# projet_pcb_nucleo_g431.net
KiCad netlist of a schematic drawn in Altium Designer
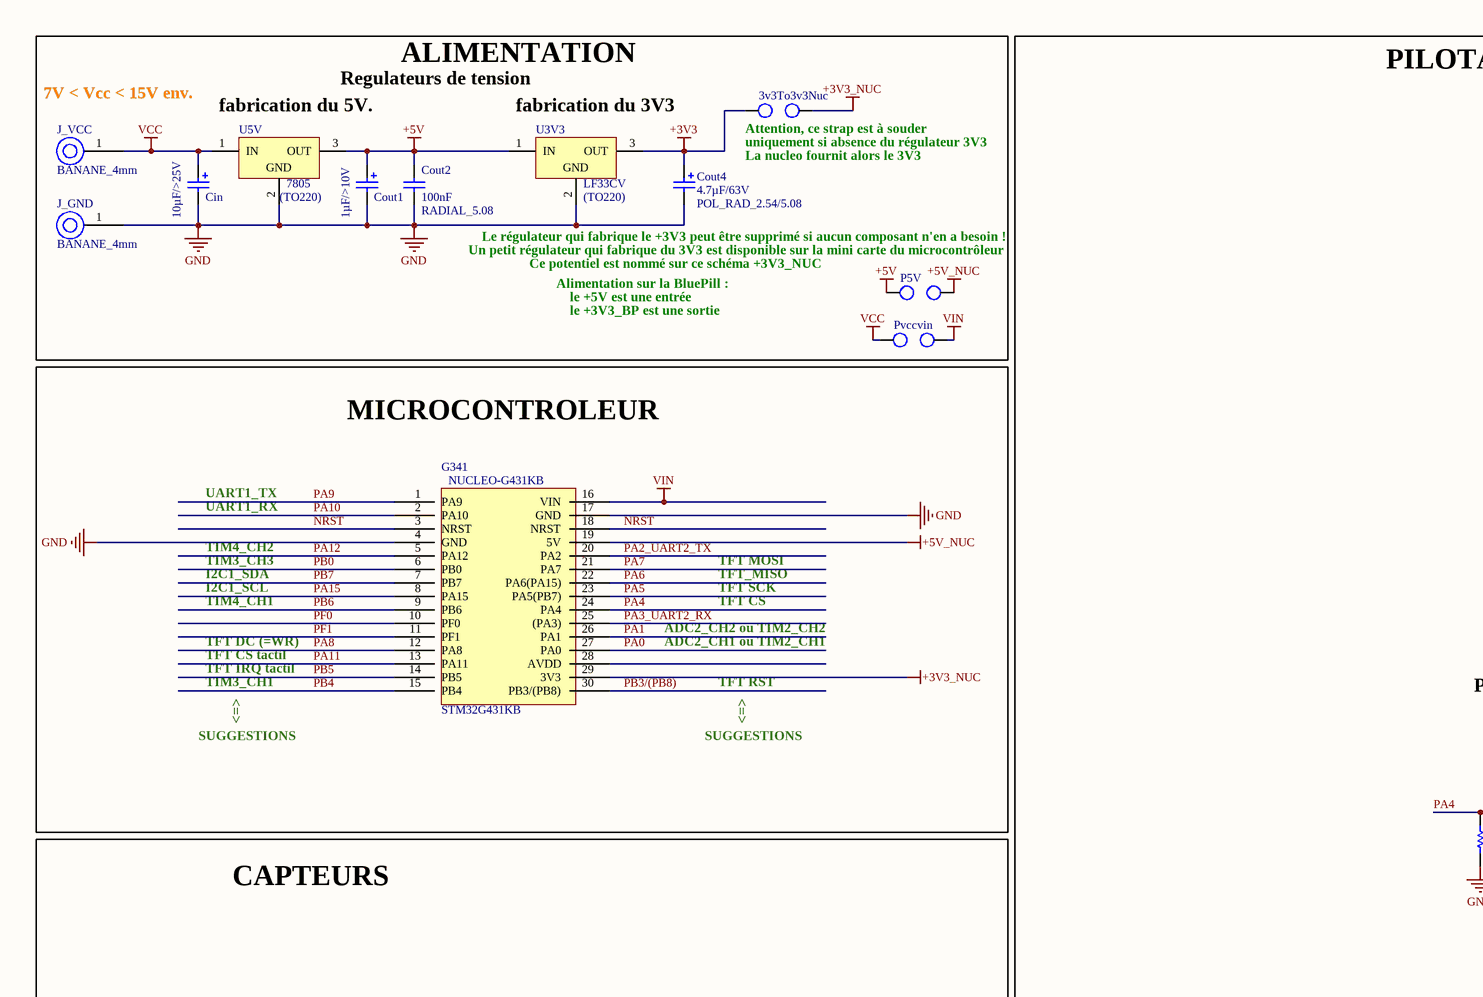
[diagram p0: projet_pcb_nucleo_g431.SchDoc, left]
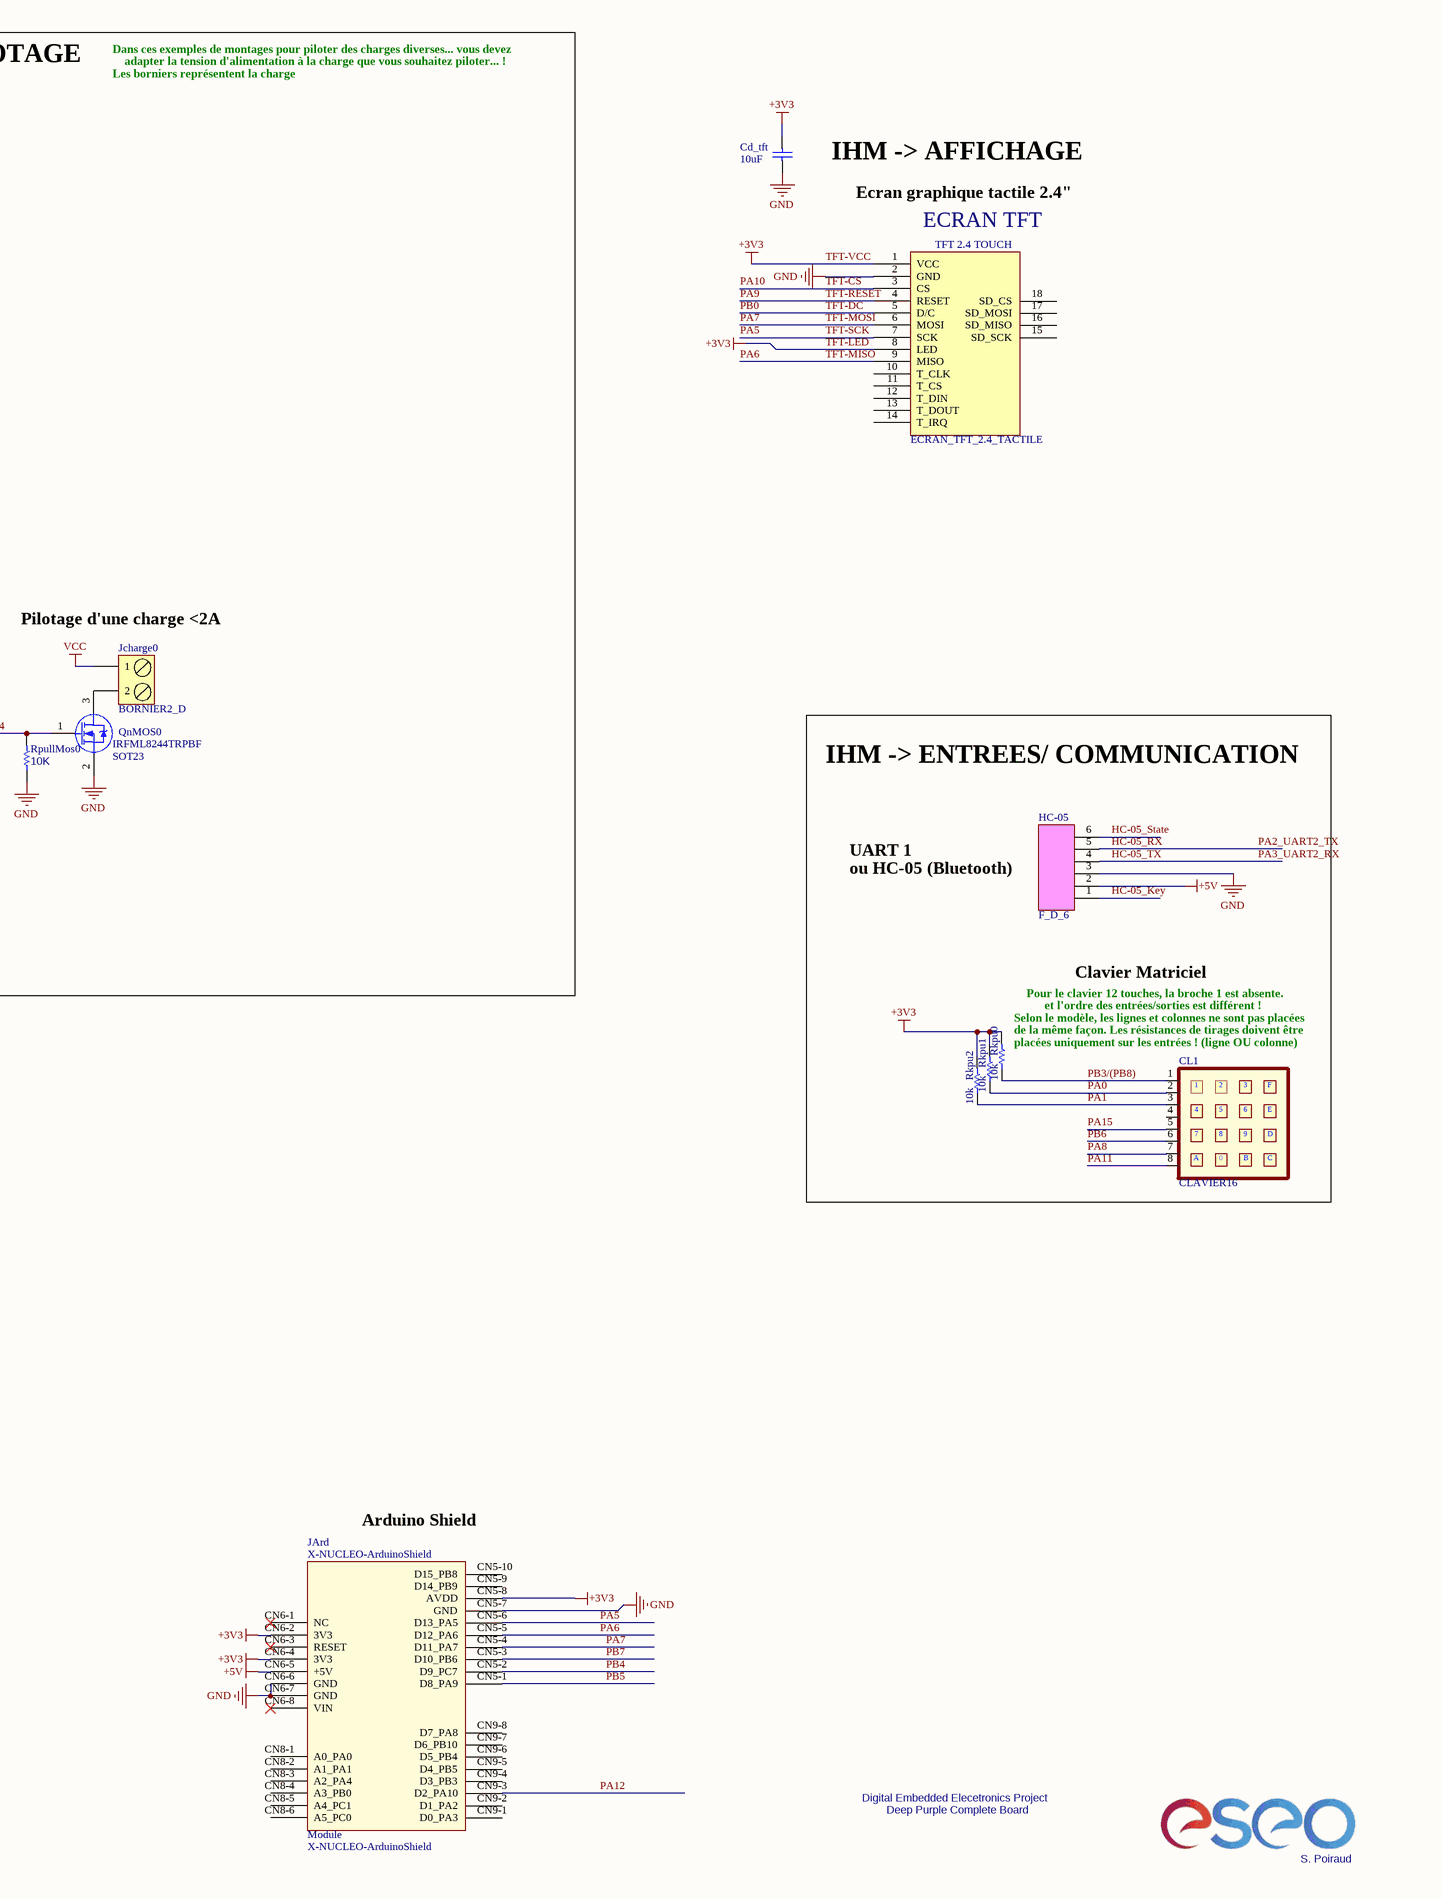
[diagram p1: projet_pcb_nucleo_g431.SchDoc, right]

(export (version "E")
  (design (tool "Eeschema 10.0.6"))
  (components
    (comp (ref "3v3To3v3Nuc")
      (value "JUMPER2")
      (footprint "BARRETTE_2_M_D")
      (description "BARRETTE 2 CONTACTS 1 RANGEE MALE DROITE")
      (libsource (lib "connecteurs") (part "JUMPER2"))
    )
    (comp (ref "Cd_tft")
      (value "10uF")
      (footprint "C0805_N")
      (description "CONDENSATEUR CMS CERAMIQUE 0805")
      (libsource (lib "composants passifs") (part "CONDENSATEUR_CMS_CER_0805"))
    )
    (comp (ref "Cin")
      (value "10µF/>25V")
      (footprint "CONDENSATEUR_POLARISE_ELECTROLYTIQUE_RADIAL_2.0/5.08")
      (description "CONDENSATEUR POLARISE ELECTROLYTIQUE RADIAL 2.0/5.08")
      (fields (field (name "Comment") "CONDENSATEUR_POL_ELECTROLY_RAD_2.0/5.08"))
      (libsource (lib "composants passifs") (part "CONDENSATEUR_POL_ELECTROLY_RAD_2.0/5.08"))
    )
    (comp (ref "CL1")
      (value "CLAVIER_16_TOUCHES")
      (footprint "CLAVIER_16_TOUCHES")
      (description "CLAVIER 16 TOUCHES")
      (fields (field (name "TYPE") "CLAVIER16"))
      (libsource (lib "commutation") (part "CLAVIER_16_TOUCHES"))
    )
    (comp (ref "Cout1")
      (value "1µF/>10V")
      (footprint "CONDENSATEUR_POLARISE_ELECTROLYTIQUE_RADIAL_2.0/5.08")
      (description "CONDENSATEUR POLARISE ELECTROLYTIQUE RADIAL 2.0/5.08")
      (fields (field (name "Comment") "CONDENSATEUR_POL_ELECTROLY_RAD_2.0/5.08"))
      (libsource (lib "composants passifs") (part "CONDENSATEUR_POL_ELECTROLY_RAD_2.0/5.08"))
    )
    (comp (ref "Cout2")
      (value "100nF")
      (footprint "CONDENSATEUR_CERAMIQUE_RADIAL_5.08")
      (description "CONDENSATEUR TRAVERSANT CERAMIQUE RADIAL 5.08mm")
      (fields (field (name "TYPE") "RADIAL_5.08") (field (name "Comment") "CONDENSATEUR_CER_RAD_5.08"))
      (libsource (lib "composants passifs") (part "CONDENSATEUR_CER_RAD_5.08"))
    )
    (comp (ref "Cout4")
      (value "4.7µF/63V")
      (footprint "CONDENSATEUR_POLARISE_ELECTROLYTIQUE_RADIAL_2.54/5.08")
      (description "CONDENSATEUR POLARISE ELECTROLYTIQUE RADIAL 2.54/5.08")
      (fields
        (field (name "TYPE") "POL_RAD_2.54/5.08")
        (field (name "Comment") "CONDENSATEUR_POL_ELECTROLY_RAD_2.54/5.08")
      )
      (libsource (lib "composants passifs") (part "CONDENSATEUR_POL_ELECTROLY_RAD_2.54/5.08"))
    )
    (comp (ref "G341")
      (value "STM32G431KB")
      (footprint "NUCLEO-G431KB")
      (libsource (lib "circuits integres") (part "G431_Nucleo"))
    )
    (comp (ref "HC-05")
      (value "BARRETTE_6 CONTACTS_1 RANGEE_FEMELLE_DROITE")
      (footprint "BARRETTE_6_F_D")
      (description "BARRETTE 6 CONTACTS 1 RANGEE FEMELLE DROITE")
      (fields (field (name "TYPE") "F_D_6"))
      (libsource (lib "connecteurs") (part "BARRETTE_6 CONTACTS_1 RANGEE_FEMELLE_DROITE"))
    )
    (comp (ref "JArd")
      (value "X-NUCLEO-ArduinoShield")
      (footprint "X-NUCLEO-ARDUINO_SHIELD")
      (libsource (lib "circuits integres") (part "X-NUCLEO-ArduinoShield"))
    )
    (comp (ref "Jcharge0")
      (value "BORNIER2 DROIT A VIS")
      (footprint "BORNIER2_A_VIS")
      (description "BORNIER 2 PLOTS DROIT A VIS 5.08mm")
      (fields (field (name "TYPE") "BORNIER2_D"))
      (libsource (lib "connecteurs") (part "BORNIER2_DROIT_A VIS"))
    )
    (comp (ref "J_GND")
      (value "DOUILLE BANANE 4mm")
      (footprint "DOUILLE_BANANE_4mm")
      (description "DOUILLE BANANE 4 mm")
      (fields (field (name "TYPE") "BANANE_4mm"))
      (libsource (lib "connecteurs") (part "DOUILLE_BANANE_4mm"))
    )
    (comp (ref "J_VCC")
      (value "DOUILLE BANANE 4mm")
      (footprint "DOUILLE_BANANE_4mm")
      (description "DOUILLE BANANE 4 mm")
      (fields (field (name "TYPE") "BANANE_4mm"))
      (libsource (lib "connecteurs") (part "DOUILLE_BANANE_4mm"))
    )
    (comp (ref "P5V")
      (value "JUMPER2")
      (footprint "BARRETTE_2_M_D")
      (description "BARRETTE 2 CONTACTS 1 RANGEE MALE DROITE")
      (libsource (lib "connecteurs") (part "JUMPER2"))
    )
    (comp (ref "Pvccvin")
      (value "JUMPER2")
      (footprint "BARRETTE_2_M_D")
      (description "BARRETTE 2 CONTACTS 1 RANGEE MALE DROITE")
      (libsource (lib "connecteurs") (part "JUMPER2"))
    )
    (comp (ref "QnMOS0")
      (value "TRANSISTOR_MOSFET-N_SOT23_GSD")
      (footprint "TRANSISTOR_MOSFET-N_SOT23_GSD")
      (description "TRANSISTOR MOSFET CANAL N BOITIER SOT23_GSD")
      (fields (field (name "TYPE") "IRFML8244TRPBF") (field (name "PACKAGE") "SOT23"))
      (libsource (lib "composants actifs") (part "TRANSISTOR_MOSFET-N_SOT23_GSD"))
    )
    (comp (ref "Rkpu0")
      (value "10k")
      (footprint "RESISTANCE_CMS_1206")
      (description "RESISTANCE CMS 1206")
      (fields (field (name "Comment") "RESISTANCE_CMS_1206"))
      (libsource (lib "composants passifs") (part "RESISTANCE_CMS_1206"))
    )
    (comp (ref "Rkpu1")
      (value "10k")
      (footprint "RESISTANCE_CMS_1206")
      (description "RESISTANCE CMS 1206")
      (fields (field (name "Comment") "RESISTANCE_CMS_1206"))
      (libsource (lib "composants passifs") (part "RESISTANCE_CMS_1206"))
    )
    (comp (ref "Rkpu2")
      (value "10k")
      (footprint "RESISTANCE_CMS_1206")
      (description "RESISTANCE CMS 1206")
      (fields (field (name "Comment") "RESISTANCE_CMS_1206"))
      (libsource (lib "composants passifs") (part "RESISTANCE_CMS_1206"))
    )
    (comp (ref "RpullMos0")
      (value "10K")
      (footprint "R1206_N")
      (description "RESISTANCE TRAVERSANTE AXIALE 1/4W")
      (fields (field (name "Comment") "RESISTANCE_AXIALE_1/4W"))
      (libsource (lib "composants passifs") (part "RESISTANCE_AXIALE_1/4W"))
    )
    (comp (ref "TFT1")
      (value "ECRAN_TFT_2.4_TACTILE")
      (footprint "ECRAN_TFT_2.4_TACTILE")
      (libsource (lib "affichage") (part "ECRAN_TFT_2.4_TACTILE"))
    )
    (comp (ref "U3V3")
      (value "REGULATEUR_TO220_78XX")
      (footprint "REGULATEUR_TO220_78XX")
      (description "REGULATEUR DE TENSION POSITIVE 78XX BOITIER TO220")
      (fields (field (name "TYPE") "LF33CV") (field (name "PACKAGE") "(TO220)"))
      (libsource (lib "composants actifs") (part "REGULATEUR_TO220_78XX"))
    )
    (comp (ref "U5V")
      (value "REGULATEUR_TO220_78XX")
      (footprint "REGULATEUR_TO220_78XX")
      (description "REGULATEUR DE TENSION POSITIVE 78XX BOITIER TO220")
      (fields (field (name "TYPE") "7805") (field (name "PACKAGE") "(TO220)"))
      (libsource (lib "composants actifs") (part "REGULATEUR_TO220_78XX"))
    )
  )
  (nets
    (net (code "1") (name "+3V3") (class "Default")
      (node (ref "3v3To3v3Nuc") (pin "1") (pinfunction "1_1") (pintype "passive"))
      (node (ref "Cd_tft") (pin "2") (pinfunction "2_2") (pintype "passive"))
      (node (ref "Cout4") (pin "1") (pinfunction "1_1") (pintype "passive"))
      (node (ref "JArd") (pin "CN5-8") (pinfunction "AVDD_CN5-8") (pintype "passive"))
      (node (ref "JArd") (pin "CN6-2") (pinfunction "3V3_CN6-2") (pintype "passive"))
      (node (ref "JArd") (pin "CN6-4") (pinfunction "3V3_CN6-4") (pintype "passive"))
      (node (ref "Rkpu0") (pin "2") (pinfunction "2_2") (pintype "passive"))
      (node (ref "Rkpu1") (pin "2") (pinfunction "2_2") (pintype "passive"))
      (node (ref "Rkpu2") (pin "2") (pinfunction "2_2") (pintype "passive"))
      (node (ref "TFT1") (pin "1") (pinfunction "VCC_1") (pintype "passive"))
      (node (ref "TFT1") (pin "8") (pinfunction "LED_8") (pintype "passive"))
      (node (ref "U3V3") (pin "3") (pinfunction "OUT_3") (pintype "power_in"))
    )
    (net (code "2") (name "+3V3_NUC") (class "Default")
      (node (ref "3v3To3v3Nuc") (pin "2") (pinfunction "2_2") (pintype "passive"))
      (node (ref "G341") (pin "29") (pinfunction "3V3_29") (pintype "passive"))
    )
    (net (code "3") (name "+5V") (class "Default")
      (node (ref "Cout1") (pin "1") (pinfunction "1_1") (pintype "passive"))
      (node (ref "Cout2") (pin "2") (pinfunction "2_2") (pintype "passive"))
      (node (ref "HC-05") (pin "2") (pinfunction "2_2") (pintype "passive"))
      (node (ref "JArd") (pin "CN6-5") (pinfunction "+5V_CN6-5") (pintype "passive"))
      (node (ref "P5V") (pin "1") (pinfunction "1_1") (pintype "passive"))
      (node (ref "U3V3") (pin "1") (pinfunction "IN_1") (pintype "power_in"))
      (node (ref "U5V") (pin "3") (pinfunction "OUT_3") (pintype "power_in"))
    )
    (net (code "4") (name "+5V_NUC") (class "Default")
      (node (ref "G341") (pin "19") (pinfunction "5V_19") (pintype "power_in"))
      (node (ref "P5V") (pin "2") (pinfunction "2_2") (pintype "passive"))
    )
    (net (code "5") (name "/HC-05_Key") (class "Default")
      (node (ref "HC-05") (pin "1") (pinfunction "1_1") (pintype "passive"))
    )
    (net (code "6") (name "/HC-05_RX") (class "Default")
      (node (ref "G341") (pin "20") (pinfunction "PA2_20") (pintype "passive"))
      (node (ref "HC-05") (pin "5") (pinfunction "5_5") (pintype "passive"))
    )
    (net (code "7") (name "/HC-05_State") (class "Default")
      (node (ref "HC-05") (pin "6") (pinfunction "6_6") (pintype "passive"))
    )
    (net (code "8") (name "/HC-05_TX") (class "Default")
      (node (ref "G341") (pin "25") (pinfunction "(PA3)_25") (pintype "passive"))
      (node (ref "HC-05") (pin "4") (pinfunction "4_4") (pintype "passive"))
    )
    (net (code "9") (name "/NRST") (class "Default")
      (node (ref "G341") (pin "18") (pinfunction "NRST_18") (pintype "passive"))
      (node (ref "G341") (pin "3") (pinfunction "NRST_3") (pintype "passive"))
    )
    (net (code "10") (name "/PA0") (class "Default")
      (node (ref "CL1") (pin "2") (pinfunction "2_2") (pintype "passive"))
      (node (ref "G341") (pin "27") (pinfunction "PA0_27") (pintype "passive"))
      (node (ref "Rkpu1") (pin "1") (pinfunction "1_1") (pintype "passive"))
    )
    (net (code "11") (name "/PA1") (class "Default")
      (node (ref "CL1") (pin "3") (pinfunction "3_3") (pintype "passive"))
      (node (ref "G341") (pin "26") (pinfunction "PA1_26") (pintype "passive"))
      (node (ref "Rkpu2") (pin "1") (pinfunction "1_1") (pintype "passive"))
    )
    (net (code "12") (name "/PA4") (class "Default")
      (node (ref "G341") (pin "24") (pinfunction "PA4_24") (pintype "passive"))
      (node (ref "QnMOS0") (pin "1") (pinfunction "G_1") (pintype "passive"))
      (node (ref "RpullMos0") (pin "2") (pinfunction "2_2") (pintype "passive"))
    )
    (net (code "13") (name "/PA5") (class "Default")
      (node (ref "G341") (pin "23") (pinfunction "PA5(PB7)_23") (pintype "passive"))
      (node (ref "JArd") (pin "CN5-6") (pinfunction "D13_PA5_CN5-6") (pintype "passive"))
      (node (ref "TFT1") (pin "7") (pinfunction "SCK_7") (pintype "passive"))
    )
    (net (code "14") (name "/PA6") (class "Default")
      (node (ref "G341") (pin "22") (pinfunction "PA6(PA15)_22") (pintype "passive"))
      (node (ref "JArd") (pin "CN5-5") (pinfunction "D12_PA6_CN5-5") (pintype "passive"))
      (node (ref "TFT1") (pin "9") (pinfunction "MISO_9") (pintype "passive"))
    )
    (net (code "15") (name "/PA7") (class "Default")
      (node (ref "G341") (pin "21") (pinfunction "PA7_21") (pintype "passive"))
      (node (ref "JArd") (pin "CN5-4") (pinfunction "D11_PA7_CN5-4") (pintype "passive"))
      (node (ref "TFT1") (pin "6") (pinfunction "MOSI_6") (pintype "passive"))
    )
    (net (code "16") (name "/PA8") (class "Default")
      (node (ref "CL1") (pin "7") (pinfunction "7_7") (pintype "passive"))
      (node (ref "G341") (pin "12") (pinfunction "PA8_12") (pintype "passive"))
    )
    (net (code "17") (name "/PA9") (class "Default")
      (node (ref "G341") (pin "1") (pinfunction "PA9_1") (pintype "passive"))
      (node (ref "TFT1") (pin "4") (pinfunction "RESET_4") (pintype "passive"))
    )
    (net (code "18") (name "/PA10") (class "Default")
      (node (ref "G341") (pin "2") (pinfunction "PA10_2") (pintype "passive"))
      (node (ref "TFT1") (pin "3") (pinfunction "CS_3") (pintype "passive"))
    )
    (net (code "19") (name "/PA11") (class "Default")
      (node (ref "CL1") (pin "8") (pinfunction "8_8") (pintype "passive"))
      (node (ref "G341") (pin "13") (pinfunction "PA11_13") (pintype "passive"))
    )
    (net (code "20") (name "/PA12") (class "Default")
      (node (ref "G341") (pin "5") (pinfunction "PA12_5") (pintype "passive"))
      (node (ref "JArd") (pin "CN9-3") (pinfunction "D2_PA10_CN9-3") (pintype "passive"))
    )
    (net (code "21") (name "/PA15") (class "Default")
      (node (ref "CL1") (pin "5") (pinfunction "5_5") (pintype "passive"))
      (node (ref "G341") (pin "8") (pinfunction "PA15_8") (pintype "passive"))
    )
    (net (code "22") (name "/PB0") (class "Default")
      (node (ref "G341") (pin "6") (pinfunction "PB0_6") (pintype "passive"))
      (node (ref "TFT1") (pin "5") (pinfunction "D/C_5") (pintype "passive"))
    )
    (net (code "23") (name "/PB3{slash}(PB8)") (class "Default")
      (node (ref "CL1") (pin "1") (pinfunction "1_1") (pintype "passive"))
      (node (ref "G341") (pin "30") (pinfunction "PB3/(PB8)_30") (pintype "passive"))
      (node (ref "Rkpu0") (pin "1") (pinfunction "1_1") (pintype "passive"))
    )
    (net (code "24") (name "/PB4") (class "Default")
      (node (ref "G341") (pin "15") (pinfunction "PB4_15") (pintype "passive"))
      (node (ref "JArd") (pin "CN5-2") (pinfunction "D9_PC7_CN5-2") (pintype "passive"))
    )
    (net (code "25") (name "/PB5") (class "Default")
      (node (ref "G341") (pin "14") (pinfunction "PB5_14") (pintype "passive"))
      (node (ref "JArd") (pin "CN5-1") (pinfunction "D8_PA9_CN5-1") (pintype "passive"))
    )
    (net (code "26") (name "/PB6") (class "Default")
      (node (ref "CL1") (pin "6") (pinfunction "6_6") (pintype "passive"))
      (node (ref "G341") (pin "9") (pinfunction "PB6_9") (pintype "passive"))
    )
    (net (code "27") (name "/PB7") (class "Default")
      (node (ref "G341") (pin "7") (pinfunction "PB7_7") (pintype "passive"))
      (node (ref "JArd") (pin "CN5-3") (pinfunction "D10_PB6_CN5-3") (pintype "passive"))
    )
    (net (code "28") (name "/PF0") (class "Default")
      (node (ref "G341") (pin "10") (pinfunction "PF0_10") (pintype "passive"))
    )
    (net (code "29") (name "/PF1") (class "Default")
      (node (ref "G341") (pin "11") (pinfunction "PF1_11") (pintype "passive"))
    )
    (net (code "30") (name "GND") (class "Default")
      (node (ref "Cd_tft") (pin "1") (pinfunction "1_1") (pintype "passive"))
      (node (ref "Cin") (pin "2") (pinfunction "2_2") (pintype "passive"))
      (node (ref "Cout1") (pin "2") (pinfunction "2_2") (pintype "passive"))
      (node (ref "Cout2") (pin "1") (pinfunction "1_1") (pintype "passive"))
      (node (ref "Cout4") (pin "2") (pinfunction "2_2") (pintype "passive"))
      (node (ref "G341") (pin "17") (pinfunction "GND_17") (pintype "power_in"))
      (node (ref "G341") (pin "4") (pinfunction "GND_4") (pintype "power_in"))
      (node (ref "HC-05") (pin "3") (pinfunction "3_3") (pintype "passive"))
      (node (ref "JArd") (pin "CN5-7") (pinfunction "GND_CN5-7") (pintype "passive"))
      (node (ref "JArd") (pin "CN6-6") (pinfunction "GND_CN6-6") (pintype "passive"))
      (node (ref "JArd") (pin "CN6-7") (pinfunction "GND_CN6-7") (pintype "passive"))
      (node (ref "J_GND") (pin "1") (pinfunction "1_1") (pintype "passive"))
      (node (ref "QnMOS0") (pin "2") (pinfunction "S_2") (pintype "passive"))
      (node (ref "RpullMos0") (pin "1") (pinfunction "1_1") (pintype "passive"))
      (node (ref "TFT1") (pin "2") (pinfunction "GND_2") (pintype "passive"))
      (node (ref "U3V3") (pin "2") (pinfunction "GND_2") (pintype "power_in"))
      (node (ref "U5V") (pin "2") (pinfunction "GND_2") (pintype "power_in"))
    )
    (net (code "31") (name "Net-(QnMOS0-D)") (class "Default")
      (node (ref "Jcharge0") (pin "2") (pinfunction "2_2") (pintype "passive"))
      (node (ref "QnMOS0") (pin "3") (pinfunction "D_3") (pintype "passive"))
    )
    (net (code "32") (name "VCC") (class "Default")
      (node (ref "Cin") (pin "1") (pinfunction "1_1") (pintype "passive"))
      (node (ref "J_VCC") (pin "1") (pinfunction "1_1") (pintype "passive"))
      (node (ref "Jcharge0") (pin "1") (pinfunction "1_1") (pintype "passive"))
      (node (ref "Pvccvin") (pin "1") (pinfunction "1_1") (pintype "passive"))
      (node (ref "U5V") (pin "1") (pinfunction "IN_1") (pintype "power_in"))
    )
    (net (code "33") (name "VIN") (class "Default")
      (node (ref "G341") (pin "16") (pinfunction "VIN_16") (pintype "power_in"))
      (node (ref "Pvccvin") (pin "2") (pinfunction "2_2") (pintype "passive"))
    )
    (net (code "34") (name "unconnected-(CL1-Pad4)") (class "Default")
      (node (ref "CL1") (pin "4") (pinfunction "4_4") (pintype "passive"))
    )
    (net (code "35") (name "unconnected-(G341-AVDD-Pad28)") (class "Default")
      (node (ref "G341") (pin "28") (pinfunction "AVDD_28") (pintype "passive"))
    )
    (net (code "36") (name "unconnected-(JArd-A0_PA0-PadCN8-1)") (class "Default")
      (node (ref "JArd") (pin "CN8-1") (pinfunction "A0_PA0_CN8-1") (pintype "passive"))
    )
    (net (code "37") (name "unconnected-(JArd-A1_PA1-PadCN8-2)") (class "Default")
      (node (ref "JArd") (pin "CN8-2") (pinfunction "A1_PA1_CN8-2") (pintype "passive"))
    )
    (net (code "38") (name "unconnected-(JArd-A2_PA4-PadCN8-3)") (class "Default")
      (node (ref "JArd") (pin "CN8-3") (pinfunction "A2_PA4_CN8-3") (pintype "passive"))
    )
    (net (code "39") (name "unconnected-(JArd-A3_PB0-PadCN8-4)") (class "Default")
      (node (ref "JArd") (pin "CN8-4") (pinfunction "A3_PB0_CN8-4") (pintype "passive"))
    )
    (net (code "40") (name "unconnected-(JArd-A4_PC1-PadCN8-5)") (class "Default")
      (node (ref "JArd") (pin "CN8-5") (pinfunction "A4_PC1_CN8-5") (pintype "passive"))
    )
    (net (code "41") (name "unconnected-(JArd-A5_PC0-PadCN8-6)") (class "Default")
      (node (ref "JArd") (pin "CN8-6") (pinfunction "A5_PC0_CN8-6") (pintype "passive"))
    )
    (net (code "42") (name "unconnected-(JArd-D0_PA3-PadCN9-1)") (class "Default")
      (node (ref "JArd") (pin "CN9-1") (pinfunction "D0_PA3_CN9-1") (pintype "passive"))
    )
    (net (code "43") (name "unconnected-(JArd-D1_PA2-PadCN9-2)") (class "Default")
      (node (ref "JArd") (pin "CN9-2") (pinfunction "D1_PA2_CN9-2") (pintype "passive"))
    )
    (net (code "44") (name "unconnected-(JArd-D3_PB3-PadCN9-4)") (class "Default")
      (node (ref "JArd") (pin "CN9-4") (pinfunction "D3_PB3_CN9-4") (pintype "passive"))
    )
    (net (code "45") (name "unconnected-(JArd-D4_PB5-PadCN9-5)") (class "Default")
      (node (ref "JArd") (pin "CN9-5") (pinfunction "D4_PB5_CN9-5") (pintype "passive"))
    )
    (net (code "46") (name "unconnected-(JArd-D5_PB4-PadCN9-6)") (class "Default")
      (node (ref "JArd") (pin "CN9-6") (pinfunction "D5_PB4_CN9-6") (pintype "passive"))
    )
    (net (code "47") (name "unconnected-(JArd-D6_PB10-PadCN9-7)") (class "Default")
      (node (ref "JArd") (pin "CN9-7") (pinfunction "D6_PB10_CN9-7") (pintype "passive"))
    )
    (net (code "48") (name "unconnected-(JArd-D7_PA8-PadCN9-8)") (class "Default")
      (node (ref "JArd") (pin "CN9-8") (pinfunction "D7_PA8_CN9-8") (pintype "passive"))
    )
    (net (code "49") (name "unconnected-(JArd-D14_PB9-PadCN5-9)") (class "Default")
      (node (ref "JArd") (pin "CN5-9") (pinfunction "D14_PB9_CN5-9") (pintype "passive"))
    )
    (net (code "50") (name "unconnected-(JArd-D15_PB8-PadCN5-10)") (class "Default")
      (node (ref "JArd") (pin "CN5-10") (pinfunction "D15_PB8_CN5-10") (pintype "passive"))
    )
    (net (code "51") (name "unconnected-(JArd-NC-PadCN6-1)") (class "Default")
      (node (ref "JArd") (pin "CN6-1") (pinfunction "NC_CN6-1") (pintype "passive+no_connect"))
    )
    (net (code "52") (name "unconnected-(JArd-RESET-PadCN6-3)") (class "Default")
      (node (ref "JArd") (pin "CN6-3") (pinfunction "RESET_CN6-3") (pintype "passive+no_connect"))
    )
    (net (code "53") (name "unconnected-(JArd-VIN-PadCN6-8)") (class "Default")
      (node (ref "JArd") (pin "CN6-8") (pinfunction "VIN_CN6-8") (pintype "passive+no_connect"))
    )
    (net (code "54") (name "unconnected-(TFT1-SD_CS-Pad18)") (class "Default")
      (node (ref "TFT1") (pin "18") (pinfunction "SD_CS_18") (pintype "passive"))
    )
    (net (code "55") (name "unconnected-(TFT1-SD_MISO-Pad16)") (class "Default")
      (node (ref "TFT1") (pin "16") (pinfunction "SD_MISO_16") (pintype "passive"))
    )
    (net (code "56") (name "unconnected-(TFT1-SD_MOSI-Pad17)") (class "Default")
      (node (ref "TFT1") (pin "17") (pinfunction "SD_MOSI_17") (pintype "passive"))
    )
    (net (code "57") (name "unconnected-(TFT1-SD_SCK-Pad15)") (class "Default")
      (node (ref "TFT1") (pin "15") (pinfunction "SD_SCK_15") (pintype "passive"))
    )
    (net (code "58") (name "unconnected-(TFT1-T_CLK-Pad10)") (class "Default")
      (node (ref "TFT1") (pin "10") (pinfunction "T_CLK_10") (pintype "passive"))
    )
    (net (code "59") (name "unconnected-(TFT1-T_CS-Pad11)") (class "Default")
      (node (ref "TFT1") (pin "11") (pinfunction "T_CS_11") (pintype "passive"))
    )
    (net (code "60") (name "unconnected-(TFT1-T_DIN-Pad12)") (class "Default")
      (node (ref "TFT1") (pin "12") (pinfunction "T_DIN_12") (pintype "passive"))
    )
    (net (code "61") (name "unconnected-(TFT1-T_DOUT-Pad13)") (class "Default")
      (node (ref "TFT1") (pin "13") (pinfunction "T_DOUT_13") (pintype "passive"))
    )
    (net (code "62") (name "unconnected-(TFT1-T_IRQ-Pad14)") (class "Default")
      (node (ref "TFT1") (pin "14") (pinfunction "T_IRQ_14") (pintype "passive"))
    )
  )
)
